# DLP.net
KiCad netlist of a schematic drawn in Altium Designer
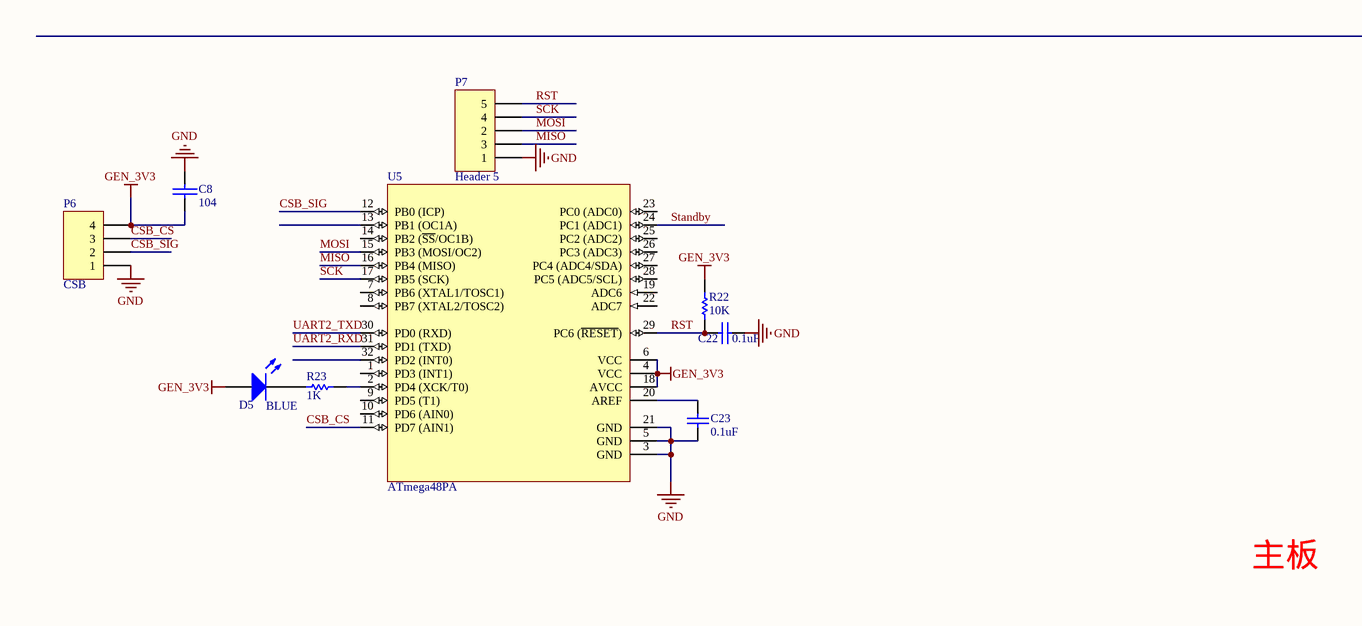
[diagram p0: DLP.SchDoc, top left]
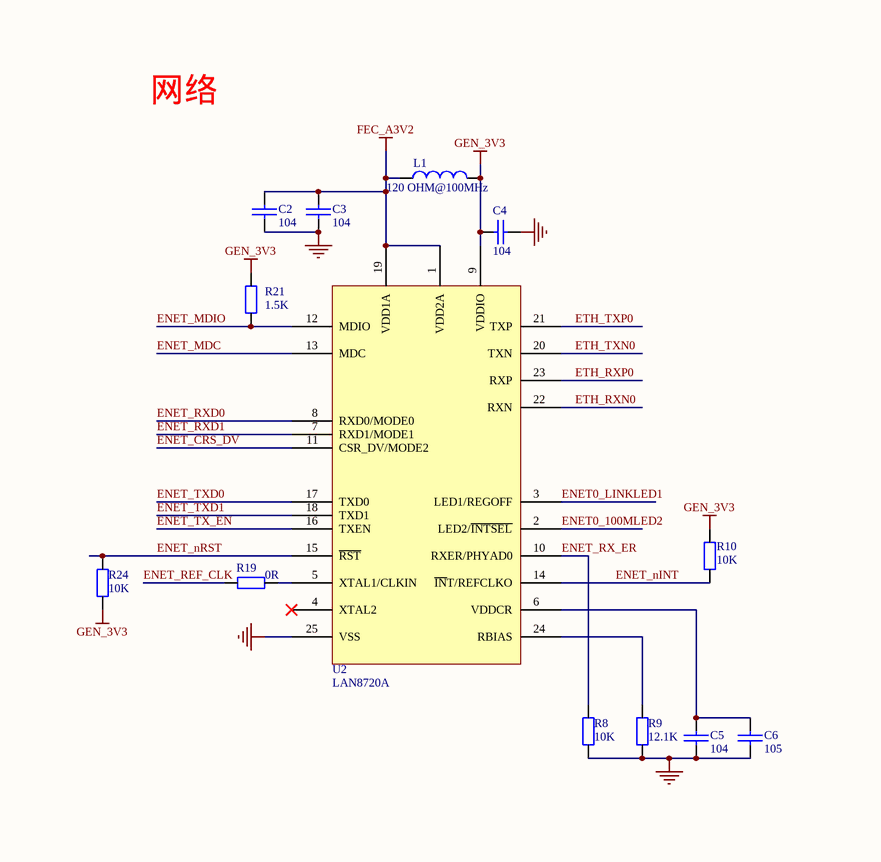
[diagram p1: DLP.SchDoc, top right]
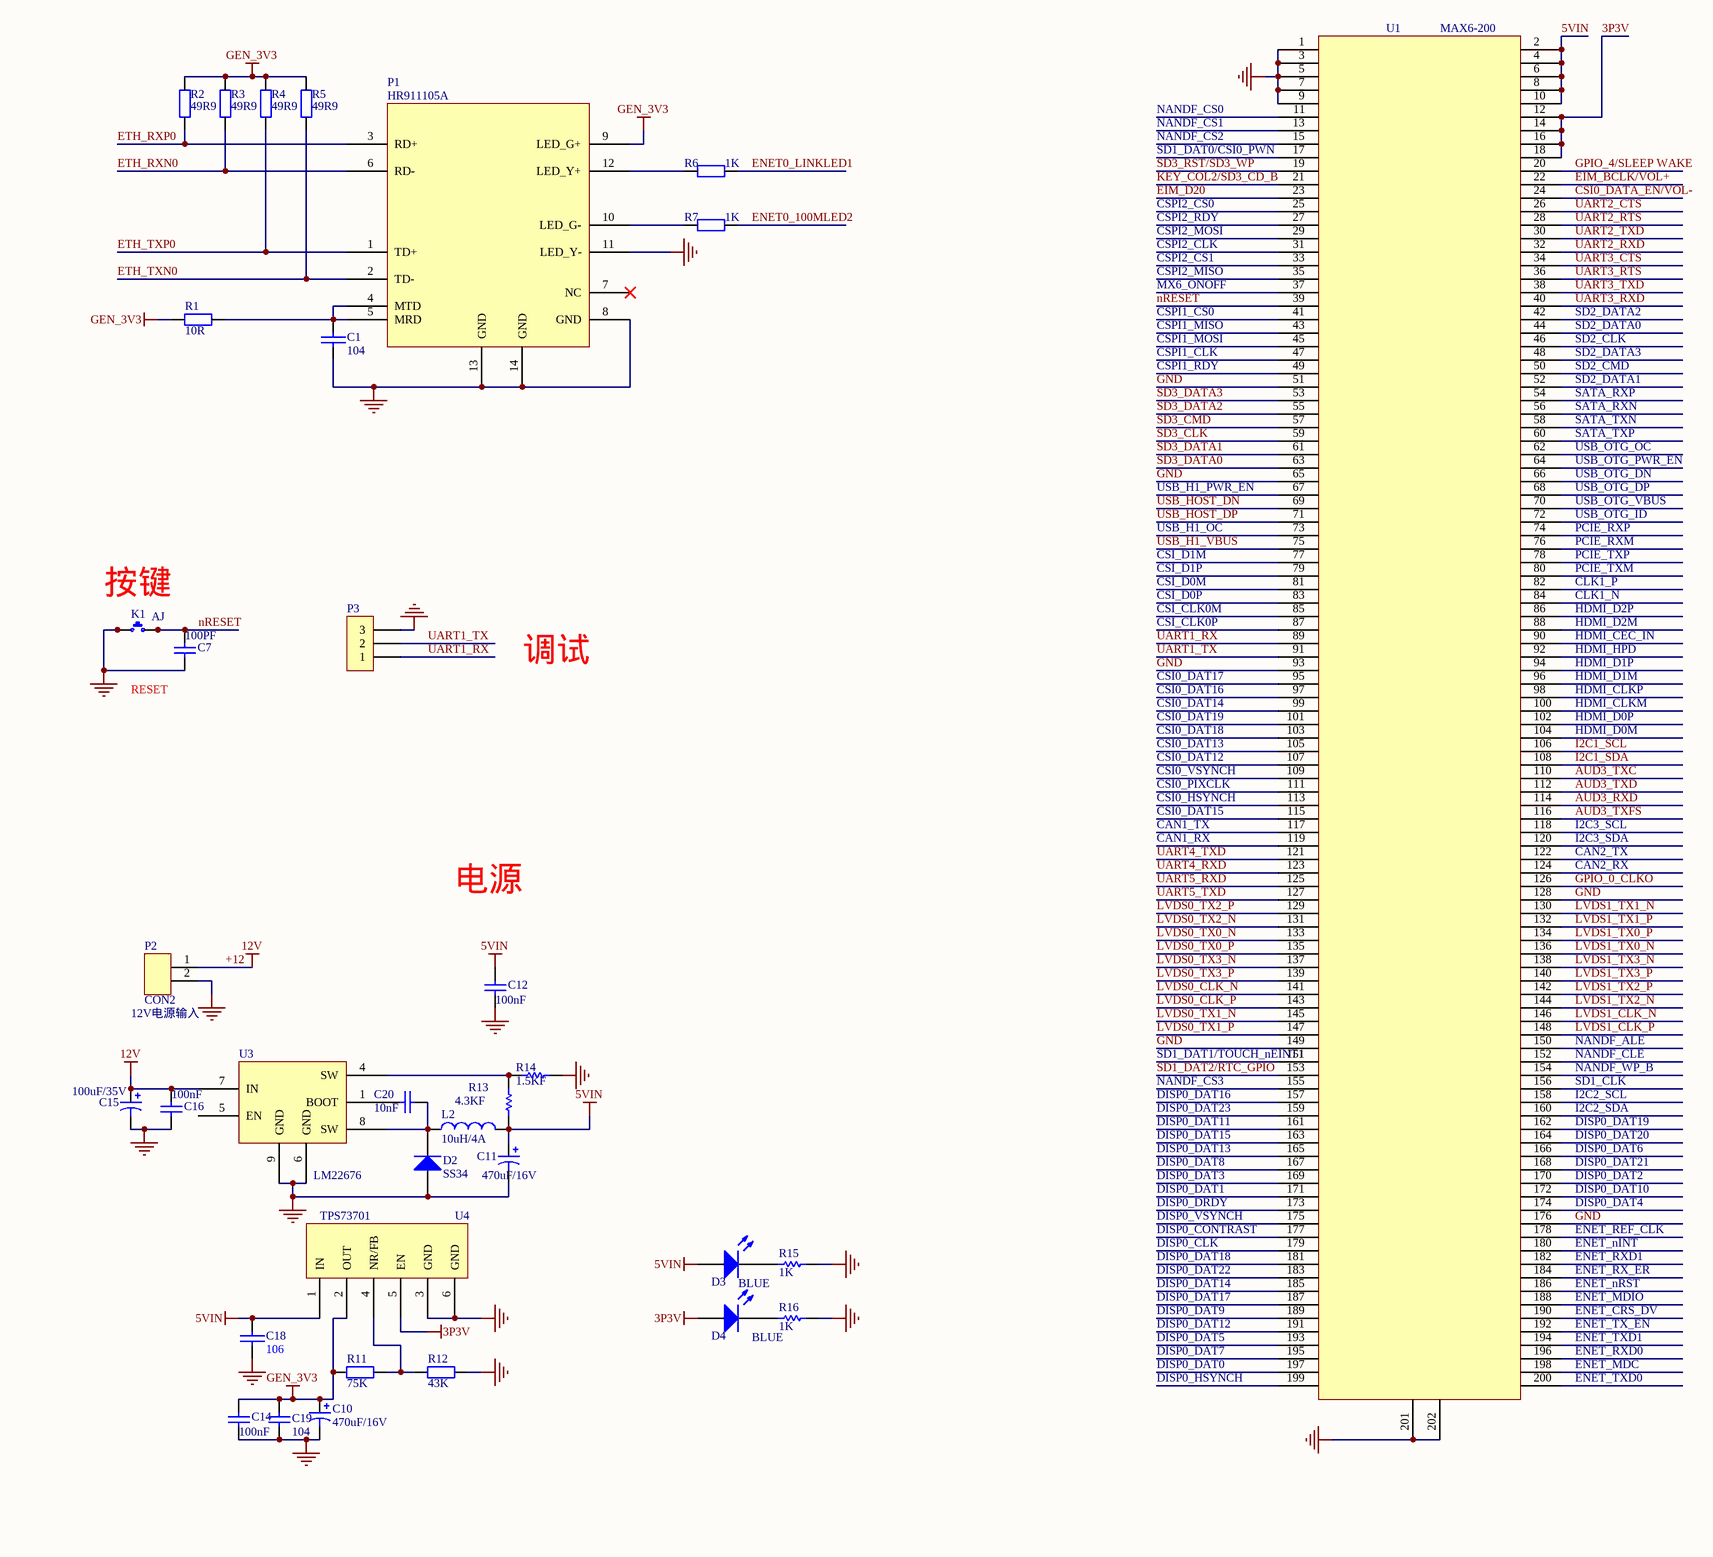
[diagram p2: DLP.SchDoc, bottom left]
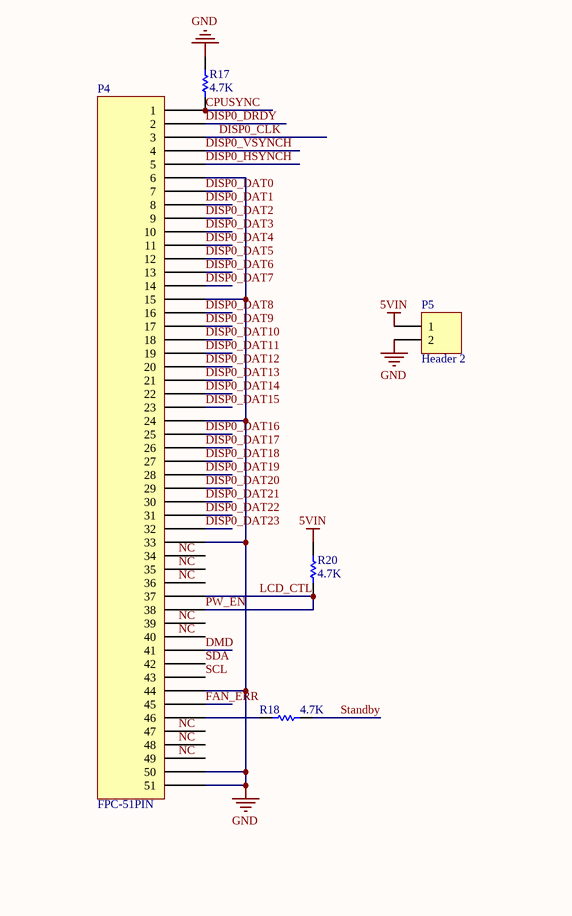
[diagram p3: DLP.SchDoc, bottom right]

(export (version "E")
  (design (tool "Eeschema 10.0.6"))
  (components
    (comp (ref "C1") (value "104") (footprint "0603") (libsource (lib "*") (part "CAP")))
    (comp (ref "C2") (value "104") (footprint "0603") (libsource (lib "*") (part "CAP")))
    (comp (ref "C3") (value "104") (footprint "0603") (libsource (lib "*") (part "CAP")))
    (comp (ref "C4") (value "104") (footprint "0603") (libsource (lib "*") (part "CAP")))
    (comp (ref "C5") (value "104") (footprint "0603") (libsource (lib "*") (part "CAP")))
    (comp (ref "C6") (value "105") (footprint "0603") (libsource (lib "*") (part "CAP")))
    (comp (ref "C7")
      (value "100PF")
      (footprint "0603")
      (description "Capacitor")
      (libsource (lib "*") (part "Cap"))
    )
    (comp (ref "C8") (value "104") (footprint "0603") (libsource (lib "*") (part "CAP")))
    (comp (ref "C10")
      (value "470uF/16V")
      (footprint "3216[1206]")
      (description "Polarized Capacitor (Radial)")
      (libsource (lib "*") (part "Cap Pol1"))
    )
    (comp (ref "C11")
      (value "470uF/16V")
      (footprint "C6.3*12")
      (description "Polarized Capacitor (Radial)")
      (libsource (lib "*") (part "Cap Pol1"))
    )
    (comp (ref "C12")
      (value "100nF")
      (footprint "0603")
      (description "Capacitor")
      (libsource (lib "*") (part "Cap"))
    )
    (comp (ref "C14")
      (value "100nF")
      (footprint "0603")
      (description "Capacitor")
      (libsource (lib "*") (part "Cap"))
    )
    (comp (ref "C15")
      (value "100uF/35V")
      (footprint "C6.3*12")
      (description "Polarized Capacitor (Radial)")
      (libsource (lib "*") (part "Cap Pol1"))
    )
    (comp (ref "C16")
      (value "100nF")
      (footprint "0603")
      (description "Capacitor")
      (libsource (lib "*") (part "Cap"))
    )
    (comp (ref "C18") (value "106") (footprint "C1206") (libsource (lib "") (part "CAP_1")))
    (comp (ref "C19")
      (value "104")
      (footprint "0603")
      (fields (field (name "PUBLISHER") "Altium Limited"))
      (libsource (lib "*") (part "Cap"))
    )
    (comp (ref "C20")
      (value "10nF")
      (footprint "0603")
      (description "Capacitor")
      (libsource (lib "*") (part "Cap"))
    )
    (comp (ref "C22")
      (value "0.1uF")
      (footprint "0603")
      (description "Capacitor")
      (fields (field (name "Comment") "Cap") (field (name "PUBLISHER") "Altium Limited"))
      (libsource (lib "Miscellaneous Devices") (part "Cap"))
    )
    (comp (ref "C23")
      (value "0.1uF")
      (footprint "0603")
      (description "Capacitor")
      (fields (field (name "Comment") "Cap") (field (name "PUBLISHER") "Altium Limited"))
      (libsource (lib "Miscellaneous Devices") (part "Cap"))
    )
    (comp (ref "D2")
      (value "SS34")
      (footprint "SMA")
      (description "3 Amp Medium Power Silicon Rectifier Diode")
      (libsource (lib "*") (part "Diode 1N5408"))
    )
    (comp (ref "D3")
      (value "BLUE")
      (footprint "0603-LED")
      (description "Typical RED, GREEN, YELLOW, AMBER GaAs LED")
      (libsource (lib "*") (part "LED2"))
    )
    (comp (ref "D4")
      (value "BLUE")
      (footprint "0603-LED")
      (description "Typical RED, GREEN, YELLOW, AMBER GaAs LED")
      (libsource (lib "*") (part "LED2"))
    )
    (comp (ref "D5")
      (value "BLUE")
      (footprint "0603-LED")
      (description "Typical RED, GREEN, YELLOW, AMBER GaAs LED")
      (libsource (lib "*") (part "LED2"))
    )
    (comp (ref "K1") (value "AJ") (footprint "4*4*1.5") (libsource (lib "*") (part "KEY_1")))
    (comp (ref "L1")
      (value "120 OHM@100MHz")
      (footprint "0603")
      (description "Inductor")
      (libsource (lib "*") (part "Inductor"))
    )
    (comp (ref "L2")
      (value "10uH/4A")
      (footprint "8040")
      (description "Inductor")
      (libsource (lib "*") (part "Inductor"))
    )
    (comp (ref "P1") (value "HR911105A") (footprint "HR911105A") (libsource (lib "*") (part "HR911105A")))
    (comp (ref "P2") (value "CON2") (footprint "PH2.0-2P") (libsource (lib "*") (part "CON2")))
    (comp (ref "P3")
      (value "~")
      (footprint "HDR1X3")
      (description "Connector")
      (libsource (lib "*") (part "CON3"))
    )
    (comp (ref "P4")
      (value "FPC-51PIN")
      (footprint "FH26-51S-0.3SHW")
      (libsource (lib "TANK") (part "FPC-51PIN"))
    )
    (comp (ref "P5")
      (value "Header 2")
      (footprint "PH2.0-2P")
      (description "Header, 2-Pin")
      (fields (field (name "PUBLISHER") "Altium Limited"))
      (libsource (lib "Miscellaneous Connectors") (part "Header 2"))
    )
    (comp (ref "P6")
      (value "CSB")
      (footprint "HDR1X4")
      (description "Header, 4-Pin")
      (fields (field (name "PUBLISHER") "Altium Limited"))
      (libsource (lib "Miscellaneous Connectors") (part "Header 4"))
    )
    (comp (ref "P7")
      (value "Header 5")
      (footprint "HDR1X5")
      (description "Header, 5-Pin")
      (fields (field (name "PUBLISHER") "Altium Limited"))
      (libsource (lib "Miscellaneous Connectors") (part "Header 5"))
    )
    (comp (ref "R1") (value "10R") (footprint "0603") (libsource (lib "*") (part "RES")))
    (comp (ref "R2") (value "49R9") (footprint "0603") (libsource (lib "*") (part "RES")))
    (comp (ref "R3") (value "49R9") (footprint "0603") (libsource (lib "*") (part "RES")))
    (comp (ref "R4") (value "49R9") (footprint "0603") (libsource (lib "*") (part "RES")))
    (comp (ref "R5") (value "49R9") (footprint "0603") (libsource (lib "*") (part "RES")))
    (comp (ref "R6") (value "1K") (footprint "0603") (libsource (lib "*") (part "RES")))
    (comp (ref "R7") (value "1K") (footprint "0603") (libsource (lib "*") (part "RES")))
    (comp (ref "R8") (value "10K") (footprint "0603") (libsource (lib "*") (part "RES")))
    (comp (ref "R9") (value "12.1K") (footprint "0603") (libsource (lib "*") (part "RES")))
    (comp (ref "R10") (value "10K") (footprint "0603") (libsource (lib "*") (part "RES")))
    (comp (ref "R11")
      (value "75K")
      (footprint "0603")
      (description "Resistor")
      (fields (field (name "PUBLISHER") "Altium Limited"))
      (libsource (lib "") (part "Res2_1"))
    )
    (comp (ref "R12")
      (value "43K")
      (footprint "0603")
      (description "Resistor")
      (fields (field (name "PUBLISHER") "Altium Limited"))
      (libsource (lib "*") (part "Res2"))
    )
    (comp (ref "R13")
      (value "4.3KF")
      (footprint "0603")
      (description "Resistor")
      (libsource (lib "*") (part "Res1"))
    )
    (comp (ref "R14")
      (value "1.5KF")
      (footprint "0603")
      (description "Resistor")
      (libsource (lib "*") (part "Res1"))
    )
    (comp (ref "R15")
      (value "1K")
      (footprint "0603")
      (description "Resistor")
      (libsource (lib "*") (part "Res1"))
    )
    (comp (ref "R16")
      (value "1K")
      (footprint "0603")
      (description "Resistor")
      (libsource (lib "*") (part "Res1"))
    )
    (comp (ref "R17")
      (value "4.7K")
      (footprint "0603")
      (description "Resistor")
      (fields (field (name "Comment") "Res1") (field (name "PUBLISHER") "Altium Limited"))
      (libsource (lib "Miscellaneous Devices") (part "Res1"))
    )
    (comp (ref "R18")
      (value "4.7K")
      (footprint "0603")
      (description "Resistor")
      (fields (field (name "Comment") "Res1") (field (name "PUBLISHER") "Altium Limited"))
      (libsource (lib "Miscellaneous Devices") (part "Res1"))
    )
    (comp (ref "R19") (value "0R") (footprint "0603") (libsource (lib "*") (part "RES")))
    (comp (ref "R20")
      (value "4.7K")
      (footprint "0603")
      (description "Resistor")
      (fields (field (name "Comment") "Res1") (field (name "PUBLISHER") "Altium Limited"))
      (libsource (lib "Miscellaneous Devices") (part "Res1"))
    )
    (comp (ref "R21") (value "1.5K") (footprint "0603R") (libsource (lib "*") (part "RES")))
    (comp (ref "R22")
      (value "10K")
      (footprint "0603")
      (description "Resistor")
      (fields (field (name "Comment") "Res1") (field (name "PUBLISHER") "Altium Limited"))
      (libsource (lib "Miscellaneous Devices") (part "Res1"))
    )
    (comp (ref "R23")
      (value "1K")
      (footprint "0603")
      (description "Resistor")
      (libsource (lib "*") (part "Res1"))
    )
    (comp (ref "R24") (value "10K") (footprint "0603") (libsource (lib "*") (part "RES")))
    (comp (ref "U1") (value "MAX6-200") (footprint "SO-DIMM 200") (libsource (lib "*") (part "MAX6-200")))
    (comp (ref "U2") (value "LAN8720A") (footprint "QFN24_4X4MM") (libsource (lib "*") (part "LAN8720A")))
    (comp (ref "U3") (value "LM22676") (footprint "SO-8HP") (libsource (lib "*") (part "LM22676")))
    (comp (ref "U4") (value "TPS73701") (footprint "SOT223-6") (libsource (lib "*") (part "TPS737")))
    (comp (ref "U5")
      (value "ATmega48PA")
      (footprint "32A_M")
      (description "8-Bit AVR Microcontroller with 8K Bytes of In-System Programmable Flash Memory")
      (fields (field (name "PUBLISHER") "Altium Limited"))
      (libsource (lib "Atmel Microcontroller 8-Bit AVR") (part "ATmega8-16AC"))
    )
  )
  (nets
    (net (code "1") (name "/AUD3_RXD") (class "Default") (node (ref "U1") (pin "114") (pintype "passive")))
    (net (code "2") (name "/AUD3_TXC") (class "Default") (node (ref "U1") (pin "110") (pintype "passive")))
    (net (code "3") (name "/AUD3_TXD") (class "Default") (node (ref "U1") (pin "112") (pintype "passive")))
    (net (code "4") (name "/AUD3_TXFS") (class "Default") (node (ref "U1") (pin "116") (pintype "passive")))
    (net (code "5") (name "/CAN1_RX") (class "Default") (node (ref "U1") (pin "119") (pintype "passive")))
    (net (code "6") (name "/CAN1_TX") (class "Default") (node (ref "U1") (pin "117") (pintype "passive")))
    (net (code "7") (name "/CAN2_RX") (class "Default") (node (ref "U1") (pin "124") (pintype "passive")))
    (net (code "8") (name "/CAN2_TX") (class "Default") (node (ref "U1") (pin "122") (pintype "passive")))
    (net (code "9") (name "/CLK1_N") (class "Default") (node (ref "U1") (pin "84") (pintype "passive")))
    (net (code "10") (name "/CLK1_P") (class "Default") (node (ref "U1") (pin "82") (pintype "passive")))
    (net (code "11") (name "/CPUSYNC") (class "Default")
      (node (ref "P4") (pin "1") (pinfunction "1_1") (pintype "passive"))
      (node (ref "R17") (pin "2") (pinfunction "2_2") (pintype "passive"))
    )
    (net (code "12") (name "/CSB_CS") (class "Default")
      (node (ref "P6") (pin "3") (pinfunction "3_3") (pintype "passive"))
      (node (ref "U5") (pin "11") (pinfunction "PD7_(AIN1)_11") (pintype "bidirectional"))
    )
    (net (code "13") (name "/CSB_SIG") (class "Default")
      (node (ref "P6") (pin "2") (pinfunction "2_2") (pintype "passive"))
      (node (ref "U5") (pin "12") (pinfunction "PB0_(ICP)_12") (pintype "bidirectional"))
    )
    (net (code "14") (name "/CSI0_DAT12") (class "Default") (node (ref "U1") (pin "107") (pintype "passive")))
    (net (code "15") (name "/CSI0_DAT13") (class "Default") (node (ref "U1") (pin "105") (pintype "passive")))
    (net (code "16") (name "/CSI0_DAT14") (class "Default") (node (ref "U1") (pin "99") (pintype "passive")))
    (net (code "17") (name "/CSI0_DAT15") (class "Default") (node (ref "U1") (pin "115") (pintype "passive")))
    (net (code "18") (name "/CSI0_DAT16") (class "Default") (node (ref "U1") (pin "97") (pintype "passive")))
    (net (code "19") (name "/CSI0_DAT17") (class "Default") (node (ref "U1") (pin "95") (pintype "passive")))
    (net (code "20") (name "/CSI0_DAT18") (class "Default") (node (ref "U1") (pin "103") (pintype "passive")))
    (net (code "21") (name "/CSI0_DAT19") (class "Default") (node (ref "U1") (pin "101") (pintype "passive")))
    (net (code "22") (name "/CSI0_DATA_EN{slash}VOL-") (class "Default")
      (node (ref "U1") (pin "24") (pintype "passive"))
    )
    (net (code "23") (name "/CSI0_HSYNCH") (class "Default")
      (node (ref "U1") (pin "113") (pintype "passive"))
    )
    (net (code "24") (name "/CSI0_PIXCLK") (class "Default")
      (node (ref "U1") (pin "111") (pintype "passive"))
    )
    (net (code "25") (name "/CSI0_VSYNCH") (class "Default")
      (node (ref "U1") (pin "109") (pintype "passive"))
    )
    (net (code "26") (name "/CSI_CLK0M") (class "Default") (node (ref "U1") (pin "85") (pintype "passive")))
    (net (code "27") (name "/CSI_CLK0P") (class "Default") (node (ref "U1") (pin "87") (pintype "passive")))
    (net (code "28") (name "/CSI_D0M") (class "Default") (node (ref "U1") (pin "81") (pintype "passive")))
    (net (code "29") (name "/CSI_D0P") (class "Default") (node (ref "U1") (pin "83") (pintype "passive")))
    (net (code "30") (name "/CSI_D1M") (class "Default") (node (ref "U1") (pin "77") (pintype "passive")))
    (net (code "31") (name "/CSI_D1P") (class "Default") (node (ref "U1") (pin "79") (pintype "passive")))
    (net (code "32") (name "/CSPI1_CLK") (class "Default") (node (ref "U1") (pin "47") (pintype "passive")))
    (net (code "33") (name "/CSPI1_CS0") (class "Default") (node (ref "U1") (pin "41") (pintype "passive")))
    (net (code "34") (name "/CSPI1_MISO") (class "Default") (node (ref "U1") (pin "43") (pintype "passive")))
    (net (code "35") (name "/CSPI1_MOSI") (class "Default") (node (ref "U1") (pin "45") (pintype "passive")))
    (net (code "36") (name "/CSPI1_RDY") (class "Default") (node (ref "U1") (pin "49") (pintype "passive")))
    (net (code "37") (name "/CSPI2_CLK") (class "Default") (node (ref "U1") (pin "31") (pintype "passive")))
    (net (code "38") (name "/CSPI2_CS0") (class "Default") (node (ref "U1") (pin "25") (pintype "passive")))
    (net (code "39") (name "/CSPI2_CS1") (class "Default") (node (ref "U1") (pin "33") (pintype "passive")))
    (net (code "40") (name "/CSPI2_MISO") (class "Default") (node (ref "U1") (pin "35") (pintype "passive")))
    (net (code "41") (name "/CSPI2_MOSI") (class "Default") (node (ref "U1") (pin "29") (pintype "passive")))
    (net (code "42") (name "/CSPI2_RDY") (class "Default") (node (ref "U1") (pin "27") (pintype "passive")))
    (net (code "43") (name "/DISP0_CLK") (class "Default")
      (node (ref "P4") (pin "3") (pinfunction "3_3") (pintype "passive"))
      (node (ref "U1") (pin "179") (pintype "passive"))
    )
    (net (code "44") (name "/DISP0_CONTRAST") (class "Default")
      (node (ref "U1") (pin "177") (pintype "passive"))
    )
    (net (code "45") (name "/DISP0_DAT0") (class "Default")
      (node (ref "P4") (pin "7") (pinfunction "7_7") (pintype "passive"))
      (node (ref "U1") (pin "197") (pintype "passive"))
    )
    (net (code "46") (name "/DISP0_DAT1") (class "Default")
      (node (ref "P4") (pin "8") (pinfunction "8_8") (pintype "passive"))
      (node (ref "U1") (pin "171") (pintype "passive"))
    )
    (net (code "47") (name "/DISP0_DAT2") (class "Default")
      (node (ref "P4") (pin "9") (pinfunction "9_9") (pintype "passive"))
      (node (ref "U1") (pin "170") (pintype "passive"))
    )
    (net (code "48") (name "/DISP0_DAT3") (class "Default")
      (node (ref "P4") (pin "10") (pinfunction "10_10") (pintype "passive"))
      (node (ref "U1") (pin "169") (pintype "passive"))
    )
    (net (code "49") (name "/DISP0_DAT4") (class "Default")
      (node (ref "P4") (pin "11") (pinfunction "11_11") (pintype "passive"))
      (node (ref "U1") (pin "174") (pintype "passive"))
    )
    (net (code "50") (name "/DISP0_DAT5") (class "Default")
      (node (ref "P4") (pin "12") (pinfunction "12_12") (pintype "passive"))
      (node (ref "U1") (pin "193") (pintype "passive"))
    )
    (net (code "51") (name "/DISP0_DAT6") (class "Default")
      (node (ref "P4") (pin "13") (pinfunction "13_13") (pintype "passive"))
      (node (ref "U1") (pin "166") (pintype "passive"))
    )
    (net (code "52") (name "/DISP0_DAT7") (class "Default")
      (node (ref "P4") (pin "14") (pinfunction "14_14") (pintype "passive"))
      (node (ref "U1") (pin "195") (pintype "passive"))
    )
    (net (code "53") (name "/DISP0_DAT8") (class "Default")
      (node (ref "P4") (pin "16") (pinfunction "16_16") (pintype "passive"))
      (node (ref "U1") (pin "167") (pintype "passive"))
    )
    (net (code "54") (name "/DISP0_DAT9") (class "Default")
      (node (ref "P4") (pin "17") (pinfunction "17_17") (pintype "passive"))
      (node (ref "U1") (pin "189") (pintype "passive"))
    )
    (net (code "55") (name "/DISP0_DAT10") (class "Default")
      (node (ref "P4") (pin "18") (pinfunction "18_18") (pintype "passive"))
      (node (ref "U1") (pin "172") (pintype "passive"))
    )
    (net (code "56") (name "/DISP0_DAT11") (class "Default")
      (node (ref "P4") (pin "19") (pinfunction "19_19") (pintype "passive"))
      (node (ref "U1") (pin "161") (pintype "passive"))
    )
    (net (code "57") (name "/DISP0_DAT12") (class "Default")
      (node (ref "P4") (pin "20") (pinfunction "20_20") (pintype "passive"))
      (node (ref "U1") (pin "191") (pintype "passive"))
    )
    (net (code "58") (name "/DISP0_DAT13") (class "Default")
      (node (ref "P4") (pin "21") (pinfunction "21_21") (pintype "passive"))
      (node (ref "U1") (pin "165") (pintype "passive"))
    )
    (net (code "59") (name "/DISP0_DAT14") (class "Default")
      (node (ref "P4") (pin "22") (pinfunction "22_22") (pintype "passive"))
      (node (ref "U1") (pin "185") (pintype "passive"))
    )
    (net (code "60") (name "/DISP0_DAT15") (class "Default")
      (node (ref "P4") (pin "23") (pinfunction "23_23") (pintype "passive"))
      (node (ref "U1") (pin "163") (pintype "passive"))
    )
    (net (code "61") (name "/DISP0_DAT16") (class "Default")
      (node (ref "P4") (pin "25") (pinfunction "25_25") (pintype "passive"))
      (node (ref "U1") (pin "157") (pintype "passive"))
    )
    (net (code "62") (name "/DISP0_DAT17") (class "Default")
      (node (ref "P4") (pin "26") (pinfunction "26_26") (pintype "passive"))
      (node (ref "U1") (pin "187") (pintype "passive"))
    )
    (net (code "63") (name "/DISP0_DAT18") (class "Default")
      (node (ref "P4") (pin "27") (pinfunction "27_27") (pintype "passive"))
      (node (ref "U1") (pin "181") (pintype "passive"))
    )
    (net (code "64") (name "/DISP0_DAT19") (class "Default")
      (node (ref "P4") (pin "28") (pinfunction "28_28") (pintype "passive"))
      (node (ref "U1") (pin "162") (pintype "passive"))
    )
    (net (code "65") (name "/DISP0_DAT20") (class "Default")
      (node (ref "P4") (pin "29") (pinfunction "29_29") (pintype "passive"))
      (node (ref "U1") (pin "164") (pintype "passive"))
    )
    (net (code "66") (name "/DISP0_DAT21") (class "Default")
      (node (ref "P4") (pin "30") (pinfunction "30_30") (pintype "passive"))
      (node (ref "U1") (pin "168") (pintype "passive"))
    )
    (net (code "67") (name "/DISP0_DAT22") (class "Default")
      (node (ref "P4") (pin "31") (pinfunction "31_31") (pintype "passive"))
      (node (ref "U1") (pin "183") (pintype "passive"))
    )
    (net (code "68") (name "/DISP0_DAT23") (class "Default")
      (node (ref "P4") (pin "32") (pinfunction "32_32") (pintype "passive"))
      (node (ref "U1") (pin "159") (pintype "passive"))
    )
    (net (code "69") (name "/DISP0_DRDY") (class "Default")
      (node (ref "P4") (pin "2") (pinfunction "2_2") (pintype "passive"))
      (node (ref "U1") (pin "173") (pintype "passive"))
    )
    (net (code "70") (name "/DISP0_HSYNCH") (class "Default")
      (node (ref "P4") (pin "5") (pinfunction "5_5") (pintype "passive"))
      (node (ref "U1") (pin "199") (pintype "passive"))
    )
    (net (code "71") (name "/DISP0_VSYNCH") (class "Default")
      (node (ref "P4") (pin "4") (pinfunction "4_4") (pintype "passive"))
      (node (ref "U1") (pin "175") (pintype "passive"))
    )
    (net (code "72") (name "/DMD") (class "Default")
      (node (ref "P4") (pin "41") (pinfunction "41_41") (pintype "passive"))
    )
    (net (code "73") (name "/EIM_BCLK{slash}VOL+") (class "Default")
      (node (ref "U1") (pin "22") (pintype "passive"))
    )
    (net (code "74") (name "/EIM_D20") (class "Default") (node (ref "U1") (pin "23") (pintype "passive")))
    (net (code "75") (name "/ENET0_100MLED2") (class "Default")
      (node (ref "R7") (pin "2") (pinfunction "2_2") (pintype "passive"))
      (node (ref "U2") (pin "2") (pinfunction "LED2/~{INTSEL}_2") (pintype "passive"))
    )
    (net (code "76") (name "/ENET0_LINKLED1") (class "Default")
      (node (ref "R6") (pin "2") (pinfunction "2_2") (pintype "passive"))
      (node (ref "U2") (pin "3") (pinfunction "LED1/REGOFF_3") (pintype "passive"))
    )
    (net (code "77") (name "/ENET_CRS_DV") (class "Default")
      (node (ref "U1") (pin "190") (pintype "passive"))
      (node (ref "U2") (pin "11") (pinfunction "CSR_DV/MODE2_11") (pintype "passive"))
    )
    (net (code "78") (name "/ENET_MDC") (class "Default")
      (node (ref "U1") (pin "198") (pintype "passive"))
      (node (ref "U2") (pin "13") (pinfunction "MDC_13") (pintype "passive"))
    )
    (net (code "79") (name "/ENET_MDIO") (class "Default")
      (node (ref "R21") (pin "1") (pinfunction "1_1") (pintype "passive"))
      (node (ref "U1") (pin "188") (pintype "passive"))
      (node (ref "U2") (pin "12") (pinfunction "MDIO_12") (pintype "passive"))
    )
    (net (code "80") (name "/ENET_REF_CLK") (class "Default")
      (node (ref "R19") (pin "2") (pinfunction "2_2") (pintype "passive"))
      (node (ref "U1") (pin "178") (pintype "passive"))
    )
    (net (code "81") (name "/ENET_RXD0") (class "Default")
      (node (ref "U1") (pin "196") (pintype "passive"))
      (node (ref "U2") (pin "8") (pinfunction "RXD0/MODE0_8") (pintype "passive"))
    )
    (net (code "82") (name "/ENET_RXD1") (class "Default")
      (node (ref "U1") (pin "182") (pintype "passive"))
      (node (ref "U2") (pin "7") (pinfunction "RXD1/MODE1_7") (pintype "passive"))
    )
    (net (code "83") (name "/ENET_RX_ER") (class "Default")
      (node (ref "R8") (pin "2") (pinfunction "2_2") (pintype "passive"))
      (node (ref "U1") (pin "184") (pintype "passive"))
      (node (ref "U2") (pin "10") (pinfunction "RXER/PHYAD0_10") (pintype "passive"))
    )
    (net (code "84") (name "/ENET_TXD0") (class "Default")
      (node (ref "U1") (pin "200") (pintype "passive"))
      (node (ref "U2") (pin "17") (pinfunction "TXD0_17") (pintype "passive"))
    )
    (net (code "85") (name "/ENET_TXD1") (class "Default")
      (node (ref "U1") (pin "194") (pintype "passive"))
      (node (ref "U2") (pin "18") (pinfunction "TXD1_18") (pintype "passive"))
    )
    (net (code "86") (name "/ENET_TX_EN") (class "Default")
      (node (ref "U1") (pin "192") (pintype "passive"))
      (node (ref "U2") (pin "16") (pinfunction "TXEN_16") (pintype "passive"))
    )
    (net (code "87") (name "/ENET_nINT") (class "Default")
      (node (ref "R10") (pin "1") (pinfunction "1_1") (pintype "passive"))
      (node (ref "U1") (pin "180") (pintype "passive"))
      (node (ref "U2") (pin "14") (pinfunction "~{IN}T/REFCLKO_14") (pintype "passive"))
    )
    (net (code "88") (name "/ENET_nRST") (class "Default")
      (node (ref "R24") (pin "2") (pinfunction "2_2") (pintype "passive"))
      (node (ref "U1") (pin "186") (pintype "passive"))
      (node (ref "U2") (pin "15") (pinfunction "~{RST}_15") (pintype "passive"))
    )
    (net (code "89") (name "/ETH_RXN0") (class "Default")
      (node (ref "P1") (pin "6") (pinfunction "RD-_6") (pintype "passive"))
      (node (ref "R3") (pin "1") (pinfunction "1_1") (pintype "passive"))
      (node (ref "U2") (pin "22") (pinfunction "RXN_22") (pintype "passive"))
    )
    (net (code "90") (name "/ETH_RXP0") (class "Default")
      (node (ref "P1") (pin "3") (pinfunction "RD+_3") (pintype "passive"))
      (node (ref "R2") (pin "1") (pinfunction "1_1") (pintype "passive"))
      (node (ref "U2") (pin "23") (pinfunction "RXP_23") (pintype "passive"))
    )
    (net (code "91") (name "/ETH_TXN0") (class "Default")
      (node (ref "P1") (pin "2") (pinfunction "TD-_2") (pintype "passive"))
      (node (ref "R5") (pin "1") (pinfunction "1_1") (pintype "passive"))
      (node (ref "U2") (pin "20") (pinfunction "TXN_20") (pintype "passive"))
    )
    (net (code "92") (name "/ETH_TXP0") (class "Default")
      (node (ref "P1") (pin "1") (pinfunction "TD+_1") (pintype "passive"))
      (node (ref "R4") (pin "1") (pinfunction "1_1") (pintype "passive"))
      (node (ref "U2") (pin "21") (pinfunction "TXP_21") (pintype "passive"))
    )
    (net (code "93") (name "/FAN_ERR") (class "Default")
      (node (ref "P4") (pin "45") (pinfunction "45_45") (pintype "passive"))
    )
    (net (code "94") (name "/GPIO_0_CLKO") (class "Default")
      (node (ref "U1") (pin "126") (pintype "passive"))
    )
    (net (code "95") (name "/GPIO_4{slash}SLEEP WAKE") (class "Default")
      (node (ref "U1") (pin "20") (pintype "passive"))
    )
    (net (code "96") (name "/HDMI_CEC_IN") (class "Default") (node (ref "U1") (pin "90") (pintype "passive")))
    (net (code "97") (name "/HDMI_CLKM") (class "Default") (node (ref "U1") (pin "100") (pintype "passive")))
    (net (code "98") (name "/HDMI_CLKP") (class "Default") (node (ref "U1") (pin "98") (pintype "passive")))
    (net (code "99") (name "/HDMI_D0M") (class "Default") (node (ref "U1") (pin "104") (pintype "passive")))
    (net (code "100") (name "/HDMI_D0P") (class "Default") (node (ref "U1") (pin "102") (pintype "passive")))
    (net (code "101") (name "/HDMI_D1M") (class "Default") (node (ref "U1") (pin "96") (pintype "passive")))
    (net (code "102") (name "/HDMI_D1P") (class "Default") (node (ref "U1") (pin "94") (pintype "passive")))
    (net (code "103") (name "/HDMI_D2M") (class "Default") (node (ref "U1") (pin "88") (pintype "passive")))
    (net (code "104") (name "/HDMI_D2P") (class "Default") (node (ref "U1") (pin "86") (pintype "passive")))
    (net (code "105") (name "/HDMI_HPD") (class "Default") (node (ref "U1") (pin "92") (pintype "passive")))
    (net (code "106") (name "/I2C1_SCL") (class "Default") (node (ref "U1") (pin "106") (pintype "passive")))
    (net (code "107") (name "/I2C1_SDA") (class "Default") (node (ref "U1") (pin "108") (pintype "passive")))
    (net (code "108") (name "/I2C2_SCL") (class "Default") (node (ref "U1") (pin "158") (pintype "passive")))
    (net (code "109") (name "/I2C2_SDA") (class "Default") (node (ref "U1") (pin "160") (pintype "passive")))
    (net (code "110") (name "/I2C3_SCL") (class "Default") (node (ref "U1") (pin "118") (pintype "passive")))
    (net (code "111") (name "/I2C3_SDA") (class "Default") (node (ref "U1") (pin "120") (pintype "passive")))
    (net (code "112") (name "/KEY_COL2{slash}SD3_CD_B") (class "Default")
      (node (ref "U1") (pin "21") (pintype "passive"))
    )
    (net (code "113") (name "/LCD_CTL") (class "Default")
      (node (ref "P4") (pin "37") (pinfunction "37_37") (pintype "passive"))
      (node (ref "P4") (pin "38") (pinfunction "38_38") (pintype "passive"))
      (node (ref "R20") (pin "2") (pinfunction "2_2") (pintype "passive"))
    )
    (net (code "114") (name "/LVDS0_CLK_N") (class "Default")
      (node (ref "U1") (pin "141") (pintype "passive"))
    )
    (net (code "115") (name "/LVDS0_CLK_P") (class "Default")
      (node (ref "U1") (pin "143") (pintype "passive"))
    )
    (net (code "116") (name "/LVDS0_TX0_N") (class "Default")
      (node (ref "U1") (pin "133") (pintype "passive"))
    )
    (net (code "117") (name "/LVDS0_TX0_P") (class "Default")
      (node (ref "U1") (pin "135") (pintype "passive"))
    )
    (net (code "118") (name "/LVDS0_TX1_N") (class "Default")
      (node (ref "U1") (pin "145") (pintype "passive"))
    )
    (net (code "119") (name "/LVDS0_TX1_P") (class "Default")
      (node (ref "U1") (pin "147") (pintype "passive"))
    )
    (net (code "120") (name "/LVDS0_TX2_N") (class "Default")
      (node (ref "U1") (pin "131") (pintype "passive"))
    )
    (net (code "121") (name "/LVDS0_TX2_P") (class "Default")
      (node (ref "U1") (pin "129") (pintype "passive"))
    )
    (net (code "122") (name "/LVDS0_TX3_N") (class "Default")
      (node (ref "U1") (pin "137") (pintype "passive"))
    )
    (net (code "123") (name "/LVDS0_TX3_P") (class "Default")
      (node (ref "U1") (pin "139") (pintype "passive"))
    )
    (net (code "124") (name "/LVDS1_CLK_N") (class "Default")
      (node (ref "U1") (pin "146") (pintype "passive"))
    )
    (net (code "125") (name "/LVDS1_CLK_P") (class "Default")
      (node (ref "U1") (pin "148") (pintype "passive"))
    )
    (net (code "126") (name "/LVDS1_TX0_N") (class "Default")
      (node (ref "U1") (pin "136") (pintype "passive"))
    )
    (net (code "127") (name "/LVDS1_TX0_P") (class "Default")
      (node (ref "U1") (pin "134") (pintype "passive"))
    )
    (net (code "128") (name "/LVDS1_TX1_N") (class "Default")
      (node (ref "U1") (pin "130") (pintype "passive"))
    )
    (net (code "129") (name "/LVDS1_TX1_P") (class "Default")
      (node (ref "U1") (pin "132") (pintype "passive"))
    )
    (net (code "130") (name "/LVDS1_TX2_N") (class "Default")
      (node (ref "U1") (pin "144") (pintype "passive"))
    )
    (net (code "131") (name "/LVDS1_TX2_P") (class "Default")
      (node (ref "U1") (pin "142") (pintype "passive"))
    )
    (net (code "132") (name "/LVDS1_TX3_N") (class "Default")
      (node (ref "U1") (pin "138") (pintype "passive"))
    )
    (net (code "133") (name "/LVDS1_TX3_P") (class "Default")
      (node (ref "U1") (pin "140") (pintype "passive"))
    )
    (net (code "134") (name "/MISO") (class "Default")
      (node (ref "P7") (pin "3") (pinfunction "3_3") (pintype "passive"))
      (node (ref "U5") (pin "16") (pinfunction "PB4_(MISO)_16") (pintype "bidirectional"))
    )
    (net (code "135") (name "/MOSI") (class "Default")
      (node (ref "P7") (pin "2") (pinfunction "2_2") (pintype "passive"))
      (node (ref "U5") (pin "15") (pinfunction "PB3_(MOSI/OC2)_15") (pintype "bidirectional"))
    )
    (net (code "136") (name "/MX6_ONOFF") (class "Default") (node (ref "U1") (pin "37") (pintype "passive")))
    (net (code "137") (name "/NANDF_ALE") (class "Default") (node (ref "U1") (pin "150") (pintype "passive")))
    (net (code "138") (name "/NANDF_CLE") (class "Default") (node (ref "U1") (pin "152") (pintype "passive")))
    (net (code "139") (name "/NANDF_CS0") (class "Default") (node (ref "U1") (pin "11") (pintype "passive")))
    (net (code "140") (name "/NANDF_CS1") (class "Default") (node (ref "U1") (pin "13") (pintype "passive")))
    (net (code "141") (name "/NANDF_CS2") (class "Default") (node (ref "U1") (pin "15") (pintype "passive")))
    (net (code "142") (name "/NANDF_CS3") (class "Default") (node (ref "U1") (pin "155") (pintype "passive")))
    (net (code "143") (name "/NANDF_WP_B") (class "Default")
      (node (ref "U1") (pin "154") (pintype "passive"))
    )
    (net (code "145") (name "/PCIE_RXM") (class "Default") (node (ref "U1") (pin "76") (pintype "passive")))
    (net (code "146") (name "/PCIE_RXP") (class "Default") (node (ref "U1") (pin "74") (pintype "passive")))
    (net (code "147") (name "/PCIE_TXM") (class "Default") (node (ref "U1") (pin "80") (pintype "passive")))
    (net (code "148") (name "/PCIE_TXP") (class "Default") (node (ref "U1") (pin "78") (pintype "passive")))
    (net (code "149") (name "/RST") (class "Default")
      (node (ref "C22") (pin "1") (pinfunction "1_1") (pintype "passive"))
      (node (ref "P7") (pin "5") (pinfunction "5_5") (pintype "passive"))
      (node (ref "R22") (pin "1") (pinfunction "1_1") (pintype "passive"))
      (node (ref "U5") (pin "29") (pinfunction "PC6_(~{RESET})_29") (pintype "bidirectional"))
    )
    (net (code "150") (name "/SATA_RXN") (class "Default") (node (ref "U1") (pin "56") (pintype "passive")))
    (net (code "151") (name "/SATA_RXP") (class "Default") (node (ref "U1") (pin "54") (pintype "passive")))
    (net (code "152") (name "/SATA_TXN") (class "Default") (node (ref "U1") (pin "58") (pintype "passive")))
    (net (code "153") (name "/SATA_TXP") (class "Default") (node (ref "U1") (pin "60") (pintype "passive")))
    (net (code "154") (name "/SCK") (class "Default")
      (node (ref "P7") (pin "4") (pinfunction "4_4") (pintype "passive"))
      (node (ref "U5") (pin "17") (pinfunction "PB5_(SCK)_17") (pintype "bidirectional"))
    )
    (net (code "155") (name "/SCL") (class "Default")
      (node (ref "P4") (pin "43") (pinfunction "43_43") (pintype "passive"))
    )
    (net (code "156") (name "/SD1_CLK") (class "Default") (node (ref "U1") (pin "156") (pintype "passive")))
    (net (code "157") (name "/SD1_DAT0{slash}CSI0_PWN") (class "Default")
      (node (ref "U1") (pin "17") (pintype "passive"))
    )
    (net (code "158") (name "/SD1_DAT1{slash}TOUCH_nEINT1") (class "Default")
      (node (ref "U1") (pin "151") (pintype "passive"))
    )
    (net (code "159") (name "/SD1_DAT2{slash}RTC_GPIO") (class "Default")
      (node (ref "U1") (pin "153") (pintype "passive"))
    )
    (net (code "160") (name "/SD2_CLK") (class "Default") (node (ref "U1") (pin "46") (pintype "passive")))
    (net (code "161") (name "/SD2_CMD") (class "Default") (node (ref "U1") (pin "50") (pintype "passive")))
    (net (code "162") (name "/SD2_DATA0") (class "Default") (node (ref "U1") (pin "44") (pintype "passive")))
    (net (code "163") (name "/SD2_DATA1") (class "Default") (node (ref "U1") (pin "52") (pintype "passive")))
    (net (code "164") (name "/SD2_DATA2") (class "Default") (node (ref "U1") (pin "42") (pintype "passive")))
    (net (code "165") (name "/SD2_DATA3") (class "Default") (node (ref "U1") (pin "48") (pintype "passive")))
    (net (code "166") (name "/SD3_CLK") (class "Default") (node (ref "U1") (pin "59") (pintype "passive")))
    (net (code "167") (name "/SD3_CMD") (class "Default") (node (ref "U1") (pin "57") (pintype "passive")))
    (net (code "168") (name "/SD3_DATA0") (class "Default") (node (ref "U1") (pin "63") (pintype "passive")))
    (net (code "169") (name "/SD3_DATA1") (class "Default") (node (ref "U1") (pin "61") (pintype "passive")))
    (net (code "170") (name "/SD3_DATA2") (class "Default") (node (ref "U1") (pin "55") (pintype "passive")))
    (net (code "171") (name "/SD3_DATA3") (class "Default") (node (ref "U1") (pin "53") (pintype "passive")))
    (net (code "172") (name "/SD3_RST{slash}SD3_WP") (class "Default")
      (node (ref "U1") (pin "19") (pintype "passive"))
    )
    (net (code "173") (name "/SDA") (class "Default")
      (node (ref "P4") (pin "42") (pinfunction "42_42") (pintype "passive"))
    )
    (net (code "174") (name "/Standby") (class "Default")
      (node (ref "R18") (pin "2") (pinfunction "2_2") (pintype "passive"))
      (node (ref "U5") (pin "24") (pinfunction "PC1_(ADC1)_24") (pintype "bidirectional"))
    )
    (net (code "175") (name "/UART1_RX") (class "Default")
      (node (ref "P3") (pin "1") (pinfunction "1_1") (pintype "passive"))
      (node (ref "U1") (pin "89") (pintype "passive"))
    )
    (net (code "176") (name "/UART1_TX") (class "Default")
      (node (ref "P3") (pin "2") (pinfunction "2_2") (pintype "passive"))
      (node (ref "U1") (pin "91") (pintype "passive"))
    )
    (net (code "177") (name "/UART2_CTS") (class "Default") (node (ref "U1") (pin "26") (pintype "passive")))
    (net (code "178") (name "/UART2_RTS") (class "Default") (node (ref "U1") (pin "28") (pintype "passive")))
    (net (code "179") (name "/UART2_RXD") (class "Default")
      (node (ref "U1") (pin "32") (pintype "passive"))
      (node (ref "U5") (pin "31") (pinfunction "PD1_(TXD)_31") (pintype "bidirectional"))
    )
    (net (code "180") (name "/UART2_TXD") (class "Default")
      (node (ref "U1") (pin "30") (pintype "passive"))
      (node (ref "U5") (pin "30") (pinfunction "PD0_(RXD)_30") (pintype "bidirectional"))
    )
    (net (code "181") (name "/UART3_CTS") (class "Default") (node (ref "U1") (pin "34") (pintype "passive")))
    (net (code "182") (name "/UART3_RTS") (class "Default") (node (ref "U1") (pin "36") (pintype "passive")))
    (net (code "183") (name "/UART3_RXD") (class "Default") (node (ref "U1") (pin "40") (pintype "passive")))
    (net (code "184") (name "/UART3_TXD") (class "Default") (node (ref "U1") (pin "38") (pintype "passive")))
    (net (code "185") (name "/UART4_RXD") (class "Default") (node (ref "U1") (pin "123") (pintype "passive")))
    (net (code "186") (name "/UART4_TXD") (class "Default") (node (ref "U1") (pin "121") (pintype "passive")))
    (net (code "187") (name "/UART5_RXD") (class "Default") (node (ref "U1") (pin "125") (pintype "passive")))
    (net (code "188") (name "/UART5_TXD") (class "Default") (node (ref "U1") (pin "127") (pintype "passive")))
    (net (code "189") (name "/USB_H1_OC") (class "Default") (node (ref "U1") (pin "73") (pintype "passive")))
    (net (code "190") (name "/USB_H1_PWR_EN") (class "Default")
      (node (ref "U1") (pin "67") (pintype "passive"))
    )
    (net (code "191") (name "/USB_H1_VBUS") (class "Default")
      (node (ref "U1") (pin "75") (pintype "passive"))
    )
    (net (code "192") (name "/USB_HOST_DN") (class "Default")
      (node (ref "U1") (pin "69") (pintype "passive"))
    )
    (net (code "193") (name "/USB_HOST_DP") (class "Default")
      (node (ref "U1") (pin "71") (pintype "passive"))
    )
    (net (code "194") (name "/USB_OTG_DN") (class "Default") (node (ref "U1") (pin "66") (pintype "passive")))
    (net (code "195") (name "/USB_OTG_DP") (class "Default") (node (ref "U1") (pin "68") (pintype "passive")))
    (net (code "196") (name "/USB_OTG_ID") (class "Default") (node (ref "U1") (pin "72") (pintype "passive")))
    (net (code "197") (name "/USB_OTG_OC") (class "Default") (node (ref "U1") (pin "62") (pintype "passive")))
    (net (code "198") (name "/USB_OTG_PWR_EN") (class "Default")
      (node (ref "U1") (pin "64") (pintype "passive"))
    )
    (net (code "199") (name "/USB_OTG_VBUS") (class "Default")
      (node (ref "U1") (pin "70") (pintype "passive"))
    )
    (net (code "200") (name "/nRESET") (class "Default")
      (node (ref "C7") (pin "2") (pinfunction "2_2") (pintype "passive"))
      (node (ref "K1") (pin "3") (pintype "passive"))
      (node (ref "K1") (pin "4") (pintype "passive"))
      (node (ref "U1") (pin "39") (pintype "passive"))
    )
    (net (code "201") (name "3P3V") (class "Default")
      (node (ref "D4") (pin "1") (pinfunction "A_1") (pintype "passive"))
      (node (ref "U1") (pin "12") (pintype "passive"))
      (node (ref "U1") (pin "14") (pintype "passive"))
      (node (ref "U1") (pin "16") (pintype "passive"))
      (node (ref "U1") (pin "18") (pintype "passive"))
      (node (ref "U4") (pin "5") (pinfunction "EN_5") (pintype "passive"))
    )
    (net (code "202") (name "5VIN") (class "Default")
      (node (ref "C11") (pin "1") (pinfunction "1_1") (pintype "passive"))
      (node (ref "C12") (pin "2") (pinfunction "2_2") (pintype "passive"))
      (node (ref "C18") (pin "1") (pintype "passive"))
      (node (ref "D3") (pin "1") (pinfunction "A_1") (pintype "passive"))
      (node (ref "L2") (pin "2") (pinfunction "2_2") (pintype "passive"))
      (node (ref "P5") (pin "1") (pinfunction "1_1") (pintype "passive"))
      (node (ref "R13") (pin "2") (pinfunction "2_2") (pintype "passive"))
      (node (ref "R20") (pin "1") (pinfunction "1_1") (pintype "passive"))
      (node (ref "U1") (pin "10") (pintype "passive"))
      (node (ref "U1") (pin "2") (pintype "passive"))
      (node (ref "U1") (pin "4") (pintype "passive"))
      (node (ref "U1") (pin "6") (pintype "passive"))
      (node (ref "U1") (pin "8") (pintype "passive"))
      (node (ref "U4") (pin "1") (pinfunction "IN_1") (pintype "passive"))
    )
    (net (code "203") (name "12V") (class "Default")
      (node (ref "C15") (pin "1") (pinfunction "1_1") (pintype "passive"))
      (node (ref "C16") (pin "2") (pinfunction "2_2") (pintype "passive"))
      (node (ref "P2") (pin "1") (pinfunction "1_1") (pintype "passive"))
      (node (ref "U3") (pin "7") (pinfunction "IN_7") (pintype "passive"))
    )
    (net (code "204") (name "FEC_A3V2") (class "Default")
      (node (ref "C2") (pin "1") (pintype "passive"))
      (node (ref "C3") (pin "1") (pintype "passive"))
      (node (ref "L1") (pin "1") (pinfunction "1_1") (pintype "passive"))
      (node (ref "U2") (pin "1") (pinfunction "VDD2A_1") (pintype "passive"))
      (node (ref "U2") (pin "19") (pinfunction "VDD1A_19") (pintype "passive"))
    )
    (net (code "205") (name "GEN_3V3") (class "Default")
      (node (ref "C10") (pin "1") (pinfunction "1_1") (pintype "passive"))
      (node (ref "C14") (pin "2") (pinfunction "2_2") (pintype "passive"))
      (node (ref "C19") (pin "2") (pinfunction "2_2") (pintype "passive"))
      (node (ref "C4") (pin "2") (pintype "passive"))
      (node (ref "C8") (pin "2") (pintype "passive"))
      (node (ref "D5") (pin "1") (pinfunction "A_1") (pintype "passive"))
      (node (ref "L1") (pin "2") (pinfunction "2_2") (pintype "passive"))
      (node (ref "P1") (pin "9") (pinfunction "LED_G+_9") (pintype "passive"))
      (node (ref "P6") (pin "4") (pinfunction "4_4") (pintype "passive"))
      (node (ref "R1") (pin "2") (pinfunction "2_2") (pintype "passive"))
      (node (ref "R10") (pin "2") (pinfunction "2_2") (pintype "passive"))
      (node (ref "R11") (pin "2") (pinfunction "2_2") (pintype "passive"))
      (node (ref "R2") (pin "2") (pinfunction "2_2") (pintype "passive"))
      (node (ref "R21") (pin "2") (pinfunction "2_2") (pintype "passive"))
      (node (ref "R22") (pin "2") (pinfunction "2_2") (pintype "passive"))
      (node (ref "R24") (pin "1") (pinfunction "1_1") (pintype "passive"))
      (node (ref "R3") (pin "2") (pinfunction "2_2") (pintype "passive"))
      (node (ref "R4") (pin "2") (pinfunction "2_2") (pintype "passive"))
      (node (ref "R5") (pin "2") (pinfunction "2_2") (pintype "passive"))
      (node (ref "U2") (pin "9") (pinfunction "VDDIO_9") (pintype "passive"))
      (node (ref "U4") (pin "2") (pinfunction "OUT_2") (pintype "passive"))
      (node (ref "U5") (pin "18") (pinfunction "AVCC_18") (pintype "power_in"))
      (node (ref "U5") (pin "4") (pinfunction "VCC_4") (pintype "power_in"))
      (node (ref "U5") (pin "6") (pinfunction "VCC_6") (pintype "power_in"))
    )
    (net (code "206") (name "GND") (class "Default")
      (node (ref "C1") (pin "2") (pintype "passive"))
      (node (ref "C10") (pin "2") (pinfunction "2_2") (pintype "passive"))
      (node (ref "C11") (pin "2") (pinfunction "2_2") (pintype "passive"))
      (node (ref "C12") (pin "1") (pinfunction "1_1") (pintype "passive"))
      (node (ref "C14") (pin "1") (pinfunction "1_1") (pintype "passive"))
      (node (ref "C15") (pin "2") (pinfunction "2_2") (pintype "passive"))
      (node (ref "C16") (pin "1") (pinfunction "1_1") (pintype "passive"))
      (node (ref "C18") (pin "2") (pintype "passive"))
      (node (ref "C19") (pin "1") (pinfunction "1_1") (pintype "passive"))
      (node (ref "C2") (pin "2") (pintype "passive"))
      (node (ref "C22") (pin "2") (pinfunction "2_2") (pintype "passive"))
      (node (ref "C23") (pin "2") (pinfunction "2_2") (pintype "passive"))
      (node (ref "C3") (pin "2") (pintype "passive"))
      (node (ref "C4") (pin "1") (pintype "passive"))
      (node (ref "C5") (pin "2") (pintype "passive"))
      (node (ref "C6") (pin "2") (pintype "passive"))
      (node (ref "C7") (pin "1") (pinfunction "1_1") (pintype "passive"))
      (node (ref "C8") (pin "1") (pintype "passive"))
      (node (ref "D2") (pin "1") (pinfunction "A_1") (pintype "passive"))
      (node (ref "K1") (pin "1") (pintype "passive"))
      (node (ref "K1") (pin "2") (pintype "passive"))
      (node (ref "P1") (pin "11") (pinfunction "LED_Y-_11") (pintype "passive"))
      (node (ref "P1") (pin "13") (pinfunction "GND_13") (pintype "passive"))
      (node (ref "P1") (pin "14") (pinfunction "GND_14") (pintype "passive"))
      (node (ref "P1") (pin "8") (pinfunction "GND_8") (pintype "passive"))
      (node (ref "P2") (pin "2") (pinfunction "2_2") (pintype "passive"))
      (node (ref "P3") (pin "3") (pinfunction "3_3") (pintype "passive"))
      (node (ref "P4") (pin "15") (pinfunction "15_15") (pintype "passive"))
      (node (ref "P4") (pin "24") (pinfunction "24_24") (pintype "passive"))
      (node (ref "P4") (pin "33") (pinfunction "33_33") (pintype "passive"))
      (node (ref "P4") (pin "44") (pinfunction "44_44") (pintype "passive"))
      (node (ref "P4") (pin "50") (pinfunction "50_50") (pintype "passive"))
      (node (ref "P4") (pin "51") (pinfunction "51_51") (pintype "passive"))
      (node (ref "P4") (pin "6") (pinfunction "6_6") (pintype "passive"))
      (node (ref "P5") (pin "2") (pinfunction "2_2") (pintype "passive"))
      (node (ref "P6") (pin "1") (pinfunction "1_1") (pintype "passive"))
      (node (ref "P7") (pin "1") (pinfunction "1_1") (pintype "passive"))
      (node (ref "R12") (pin "2") (pinfunction "2_2") (pintype "passive"))
      (node (ref "R14") (pin "2") (pinfunction "2_2") (pintype "passive"))
      (node (ref "R15") (pin "1") (pinfunction "1_1") (pintype "passive"))
      (node (ref "R16") (pin "1") (pinfunction "1_1") (pintype "passive"))
      (node (ref "R17") (pin "1") (pinfunction "1_1") (pintype "passive"))
      (node (ref "R8") (pin "1") (pinfunction "1_1") (pintype "passive"))
      (node (ref "R9") (pin "1") (pinfunction "1_1") (pintype "passive"))
      (node (ref "U1") (pin "1") (pintype "passive"))
      (node (ref "U1") (pin "128") (pintype "passive"))
      (node (ref "U1") (pin "149") (pintype "passive"))
      (node (ref "U1") (pin "176") (pintype "passive"))
      (node (ref "U1") (pin "201") (pintype "passive"))
      (node (ref "U1") (pin "202") (pintype "passive"))
      (node (ref "U1") (pin "3") (pintype "passive"))
      (node (ref "U1") (pin "5") (pintype "passive"))
      (node (ref "U1") (pin "51") (pintype "passive"))
      (node (ref "U1") (pin "65") (pintype "passive"))
      (node (ref "U1") (pin "7") (pintype "passive"))
      (node (ref "U1") (pin "9") (pintype "passive"))
      (node (ref "U1") (pin "93") (pintype "passive"))
      (node (ref "U2") (pin "25") (pinfunction "VSS_25") (pintype "passive"))
      (node (ref "U3") (pin "6") (pinfunction "GND_6") (pintype "passive"))
      (node (ref "U3") (pin "9") (pinfunction "GND_9") (pintype "passive"))
      (node (ref "U4") (pin "3") (pinfunction "GND_3") (pintype "passive"))
      (node (ref "U4") (pin "6") (pinfunction "GND_6") (pintype "passive"))
      (node (ref "U5") (pin "21") (pinfunction "GND_21") (pintype "power_in"))
      (node (ref "U5") (pin "3") (pinfunction "GND_3") (pintype "power_in"))
      (node (ref "U5") (pin "5") (pinfunction "GND_5") (pintype "power_in"))
    )
    (net (code "207") (name "Net-(D2-K)") (class "Default")
      (node (ref "C20") (pin "1") (pinfunction "1_1") (pintype "passive"))
      (node (ref "D2") (pin "2") (pinfunction "K_2") (pintype "passive"))
      (node (ref "L2") (pin "1") (pinfunction "1_1") (pintype "passive"))
      (node (ref "U3") (pin "8") (pinfunction "SW_8") (pintype "passive"))
    )
    (net (code "208") (name "Net-(D3-K)") (class "Default")
      (node (ref "D3") (pin "2") (pinfunction "K_2") (pintype "passive"))
      (node (ref "R15") (pin "2") (pinfunction "2_2") (pintype "passive"))
    )
    (net (code "209") (name "Net-(D4-K)") (class "Default")
      (node (ref "D4") (pin "2") (pinfunction "K_2") (pintype "passive"))
      (node (ref "R16") (pin "2") (pinfunction "2_2") (pintype "passive"))
    )
    (net (code "210") (name "Net-(D5-K)") (class "Default")
      (node (ref "D5") (pin "2") (pinfunction "K_2") (pintype "passive"))
      (node (ref "R23") (pin "2") (pinfunction "2_2") (pintype "passive"))
    )
    (net (code "211") (name "Net-(P1-LED_G-)") (class "Default")
      (node (ref "P1") (pin "10") (pinfunction "LED_G-_10") (pintype "passive"))
      (node (ref "R7") (pin "1") (pinfunction "1_1") (pintype "passive"))
    )
    (net (code "212") (name "Net-(P1-LED_Y+)") (class "Default")
      (node (ref "P1") (pin "12") (pinfunction "LED_Y+_12") (pintype "passive"))
      (node (ref "R6") (pin "1") (pinfunction "1_1") (pintype "passive"))
    )
    (net (code "213") (name "Net-(P1-MRD)") (class "Default")
      (node (ref "C1") (pin "1") (pintype "passive"))
      (node (ref "P1") (pin "4") (pinfunction "MTD_4") (pintype "passive"))
      (node (ref "P1") (pin "5") (pinfunction "MRD_5") (pintype "passive"))
      (node (ref "R1") (pin "1") (pinfunction "1_1") (pintype "passive"))
    )
    (net (code "214") (name "Net-(P4-Pad46)") (class "Default")
      (node (ref "P4") (pin "46") (pinfunction "46_46") (pintype "passive"))
      (node (ref "R18") (pin "1") (pinfunction "1_1") (pintype "passive"))
    )
    (net (code "215") (name "Net-(R13-Pad1)") (class "Default")
      (node (ref "R13") (pin "1") (pinfunction "1_1") (pintype "passive"))
      (node (ref "R14") (pin "1") (pinfunction "1_1") (pintype "passive"))
      (node (ref "U3") (pin "4") (pinfunction "SW_4") (pintype "passive"))
    )
    (net (code "216") (name "Net-(U2-RBIAS)") (class "Default")
      (node (ref "R9") (pin "2") (pinfunction "2_2") (pintype "passive"))
      (node (ref "U2") (pin "24") (pinfunction "RBIAS_24") (pintype "passive"))
    )
    (net (code "217") (name "Net-(U2-VDDCR)") (class "Default")
      (node (ref "C5") (pin "1") (pintype "passive"))
      (node (ref "C6") (pin "1") (pintype "passive"))
      (node (ref "U2") (pin "6") (pinfunction "VDDCR_6") (pintype "passive"))
    )
    (net (code "218") (name "Net-(U2-XTAL1{slash}CLKIN)") (class "Default")
      (node (ref "R19") (pin "1") (pinfunction "1_1") (pintype "passive"))
      (node (ref "U2") (pin "5") (pinfunction "XTAL1/CLKIN_5") (pintype "passive"))
    )
    (net (code "219") (name "Net-(U3-BOOT)") (class "Default")
      (node (ref "C20") (pin "2") (pinfunction "2_2") (pintype "passive"))
      (node (ref "U3") (pin "1") (pinfunction "BOOT_1") (pintype "passive"))
    )
    (net (code "220") (name "Net-(U4-NR{slash}FB)") (class "Default")
      (node (ref "R11") (pin "1") (pinfunction "1_1") (pintype "passive"))
      (node (ref "R12") (pin "1") (pinfunction "1_1") (pintype "passive"))
      (node (ref "U4") (pin "4") (pinfunction "NR/FB_4") (pintype "passive"))
    )
    (net (code "221") (name "Net-(U5-AREF)") (class "Default")
      (node (ref "C23") (pin "1") (pinfunction "1_1") (pintype "passive"))
      (node (ref "U5") (pin "20") (pinfunction "AREF_20") (pintype "passive"))
    )
    (net (code "222") (name "Net-(U5-PD4_(XCK{slash}T0))") (class "Default")
      (node (ref "R23") (pin "1") (pinfunction "1_1") (pintype "passive"))
      (node (ref "U5") (pin "2") (pinfunction "PD4_(XCK/T0)_2") (pintype "bidirectional"))
    )
    (net (code "223") (name "unconnected-(P1-NC-Pad7)") (class "Default")
      (node (ref "P1") (pin "7") (pinfunction "NC_7") (pintype "passive+no_connect"))
    )
    (net (code "224") (name "unconnected-(P4-Pad34)") (class "Default")
      (node (ref "P4") (pin "34") (pinfunction "34_34") (pintype "passive"))
    )
    (net (code "225") (name "unconnected-(P4-Pad35)") (class "Default")
      (node (ref "P4") (pin "35") (pinfunction "35_35") (pintype "passive"))
    )
    (net (code "226") (name "unconnected-(P4-Pad36)") (class "Default")
      (node (ref "P4") (pin "36") (pinfunction "36_36") (pintype "passive"))
    )
    (net (code "227") (name "unconnected-(P4-Pad39)") (class "Default")
      (node (ref "P4") (pin "39") (pinfunction "39_39") (pintype "passive"))
    )
    (net (code "228") (name "unconnected-(P4-Pad40)") (class "Default")
      (node (ref "P4") (pin "40") (pinfunction "40_40") (pintype "passive"))
    )
    (net (code "229") (name "unconnected-(P4-Pad47)") (class "Default")
      (node (ref "P4") (pin "47") (pinfunction "47_47") (pintype "passive"))
    )
    (net (code "230") (name "unconnected-(P4-Pad48)") (class "Default")
      (node (ref "P4") (pin "48") (pinfunction "48_48") (pintype "passive"))
    )
    (net (code "231") (name "unconnected-(P4-Pad49)") (class "Default")
      (node (ref "P4") (pin "49") (pinfunction "49_49") (pintype "passive"))
    )
    (net (code "232") (name "unconnected-(U2-XTAL2-Pad4)") (class "Default")
      (node (ref "U2") (pin "4") (pinfunction "XTAL2_4") (pintype "passive+no_connect"))
    )
    (net (code "233") (name "unconnected-(U3-EN-Pad5)") (class "Default")
      (node (ref "U3") (pin "5") (pinfunction "EN_5") (pintype "passive"))
    )
    (net (code "234") (name "unconnected-(U5-ADC6-Pad19)") (class "Default")
      (node (ref "U5") (pin "19") (pinfunction "ADC6_19") (pintype "input"))
    )
    (net (code "235") (name "unconnected-(U5-ADC7-Pad22)") (class "Default")
      (node (ref "U5") (pin "22") (pinfunction "ADC7_22") (pintype "input"))
    )
    (net (code "236") (name "unconnected-(U5-PB1_(OC1A)-Pad13)") (class "Default")
      (node (ref "U5") (pin "13") (pinfunction "PB1_(OC1A)_13") (pintype "bidirectional"))
    )
    (net (code "237") (name "unconnected-(U5-PB2_(~{SS}{slash}OC1B)-Pad14)") (class "Default")
      (node (ref "U5") (pin "14") (pinfunction "PB2_(~{SS}/OC1B)_14") (pintype "bidirectional"))
    )
    (net (code "238") (name "unconnected-(U5-PB6_(XTAL1{slash}TOSC1)-Pad7)") (class "Default")
      (node (ref "U5") (pin "7") (pinfunction "PB6_(XTAL1/TOSC1)_7") (pintype "bidirectional"))
    )
    (net (code "239") (name "unconnected-(U5-PB7_(XTAL2{slash}TOSC2)-Pad8)") (class "Default")
      (node (ref "U5") (pin "8") (pinfunction "PB7_(XTAL2/TOSC2)_8") (pintype "bidirectional"))
    )
    (net (code "240") (name "unconnected-(U5-PC0_(ADC0)-Pad23)") (class "Default")
      (node (ref "U5") (pin "23") (pinfunction "PC0_(ADC0)_23") (pintype "bidirectional"))
    )
    (net (code "241") (name "unconnected-(U5-PC2_(ADC2)-Pad25)") (class "Default")
      (node (ref "U5") (pin "25") (pinfunction "PC2_(ADC2)_25") (pintype "bidirectional"))
    )
    (net (code "242") (name "unconnected-(U5-PC3_(ADC3)-Pad26)") (class "Default")
      (node (ref "U5") (pin "26") (pinfunction "PC3_(ADC3)_26") (pintype "bidirectional"))
    )
    (net (code "243") (name "unconnected-(U5-PC4_(ADC4{slash}SDA)-Pad27)") (class "Default")
      (node (ref "U5") (pin "27") (pinfunction "PC4_(ADC4/SDA)_27") (pintype "bidirectional"))
    )
    (net (code "244") (name "unconnected-(U5-PC5_(ADC5{slash}SCL)-Pad28)") (class "Default")
      (node (ref "U5") (pin "28") (pinfunction "PC5_(ADC5/SCL)_28") (pintype "bidirectional"))
    )
    (net (code "245") (name "unconnected-(U5-PD2_(INT0)-Pad32)") (class "Default")
      (node (ref "U5") (pin "32") (pinfunction "PD2_(INT0)_32") (pintype "bidirectional"))
    )
    (net (code "246") (name "unconnected-(U5-PD3_(INT1)-Pad1)") (class "Default")
      (node (ref "U5") (pin "1") (pinfunction "PD3_(INT1)_1") (pintype "bidirectional"))
    )
    (net (code "247") (name "unconnected-(U5-PD5_(T1)-Pad9)") (class "Default")
      (node (ref "U5") (pin "9") (pinfunction "PD5_(T1)_9") (pintype "bidirectional"))
    )
    (net (code "248") (name "unconnected-(U5-PD6_(AIN0)-Pad10)") (class "Default")
      (node (ref "U5") (pin "10") (pinfunction "PD6_(AIN0)_10") (pintype "bidirectional"))
    )
  )
)
